# POWER.net
KiCad netlist of a schematic drawn in Altium Designer
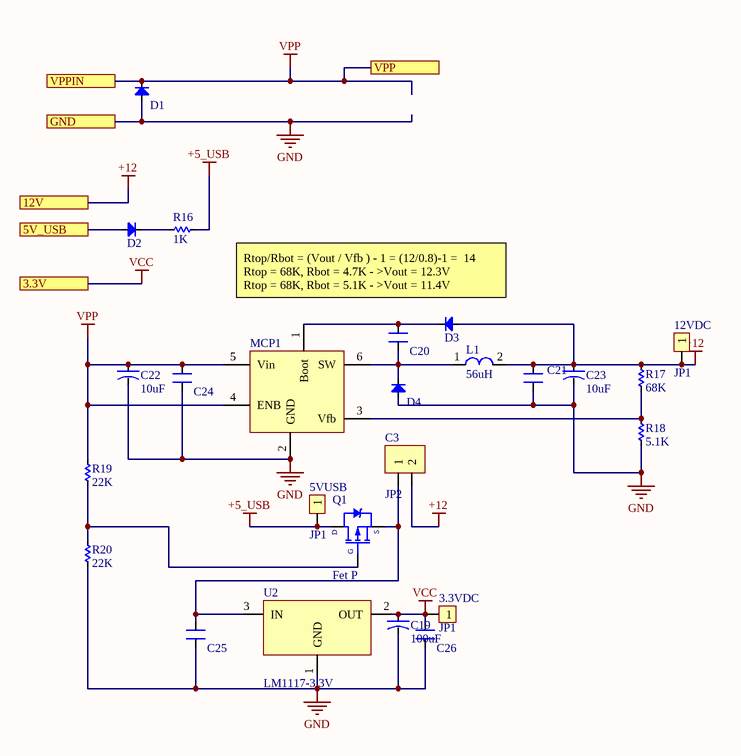
[diagram p0: POWER.SchDoc]

(export (version "E")
  (design (tool "Eeschema 10.0.6"))
  (components
    (comp (ref "3.3VDC")
      (value "JP1")
      (footprint "JP1-D1T")
      (description "WR-PHD 2.54 mm Angled Socket Header")
      (fields
        (field (name "MANUFACTURER") "Würth Elektronik eiSos GmbH")
        (field (name "PARTNO") "613002143121")
        (field (name "CREATED BY") "Karrer Zheng")
      )
      (libsource (lib "LIBRARY") (part "JP1"))
    )
    (comp (ref "5VUSB")
      (value "JP1")
      (footprint "JP1-D1T")
      (description "WR-PHD 2.54 mm Angled Socket Header")
      (fields
        (field (name "MANUFACTURER") "Würth Elektronik eiSos GmbH")
        (field (name "PARTNO") "613002143121")
        (field (name "CREATED BY") "Karrer Zheng")
      )
      (libsource (lib "") (part "JP1_1"))
    )
    (comp (ref "12VDC")
      (value "JP1")
      (footprint "JP1-D1T")
      (description "WR-PHD 2.54 mm Angled Socket Header")
      (fields
        (field (name "MANUFACTURER") "Würth Elektronik eiSos GmbH")
        (field (name "PARTNO") "613002143121")
        (field (name "CREATED BY") "Karrer Zheng")
      )
      (libsource (lib "") (part "JP1_1"))
    )
    (comp (ref "C3")
      (value "JP2")
      (footprint "JP2-CLOSED")
      (description "WR-PHD 2.54 mm Angled Socket Header")
      (fields
        (field (name "MANUFACTURER") "Würth Elektronik eiSos GmbH")
        (field (name "PARTNO") "613002143121")
        (field (name "CREATED BY") "Karrer Zheng")
      )
      (libsource (lib "LIBRARY") (part "JP2"))
    )
    (comp (ref "C19")
      (value "100uF")
      (footprint "CAP-ALU-SMD-D")
      (description "Polarized Capacitor (Axial)")
      (fields (field (name "PUBLISHER") "Altium Limited"))
      (libsource (lib "LIBRARY") (part "CN-ALU-SMD"))
    )
    (comp (ref "C20") (value "CN") (footprint "CN-SMD-0603_big") (libsource (lib "nhan") (part "CN")))
    (comp (ref "C21") (value "CN") (footprint "CN-SMD-0603_big") (libsource (lib "nhan") (part "CN")))
    (comp (ref "C22")
      (value "10uF")
      (footprint "CAP-ALU-SMD-6.3x7.7x2.2")
      (description "Polarized Capacitor (Axial)")
      (fields (field (name "PUBLISHER") "Altium Limited"))
      (libsource (lib "LIBRARY") (part "CN-ALU-SMD"))
    )
    (comp (ref "C23")
      (value "10uF")
      (footprint "CAP-ALU-SMD-6.3x7.7x2.2")
      (description "Polarized Capacitor (Axial)")
      (fields (field (name "PUBLISHER") "Altium Limited"))
      (libsource (lib "LIBRARY") (part "CN-ALU-SMD"))
    )
    (comp (ref "C24") (value "CN") (footprint "CN-SMD-0603_big") (libsource (lib "nhan") (part "CN")))
    (comp (ref "C25") (value "CN") (footprint "CN-SMD-0603_big") (libsource (lib "nhan") (part "CN")))
    (comp (ref "C26") (value "CN") (footprint "CN-SMD-0603_big") (libsource (lib "nhan") (part "CN")))
    (comp (ref "D1")
      (value "RB160M-60")
      (footprint "DIO-SMD-214AC")
      (description "Default Diode")
      (fields (field (name "PUBLISHER") "Altium Limited"))
      (libsource (lib "nhan") (part "Diode"))
    )
    (comp (ref "D2")
      (value "Diode")
      (footprint "DIO-SMD-123")
      (description "Default Diode")
      (fields (field (name "PUBLISHER") "Altium Limited"))
      (libsource (lib "nhan") (part "Diode"))
    )
    (comp (ref "D3")
      (value "Diode")
      (footprint "DIO-SMD-123")
      (description "Default Diode")
      (fields (field (name "PUBLISHER") "Altium Limited"))
      (libsource (lib "nhan") (part "Diode"))
    )
    (comp (ref "D4")
      (value "Diode")
      (footprint "DIO-SMD-123")
      (description "Default Diode")
      (fields (field (name "PUBLISHER") "Altium Limited"))
      (libsource (lib "nhan") (part "Diode"))
    )
    (comp (ref "L1")
      (value "56uH")
      (footprint "L_SMD")
      (description "https://www.thegioiic.com/products/cuon-cam-68uh-cd75-smd-7-8x7-5x5-0")
      (fields
        (field (name "PARTNO") "78477010")
        (field (name "MANUFACTURER") "Wurth Elektronik")
        (field (name "CREATED BY") "Baojun Chen")
      )
      (libsource (lib "nhan") (part "L-SMD-1"))
    )
    (comp (ref "MCP1") (value "MCP16331") (footprint "SOT23-6-") (libsource (lib "nhan") (part "MCP16331")))
    (comp (ref "Q1")
      (value "Fet P")
      (footprint "SOT23F")
      (description "HEXFET P-Channel Power MOSFET")
      (libsource (lib "nhan") (part "Fet P"))
    )
    (comp (ref "R16") (value "1K") (footprint "RES-SMD-0603_BIG") (libsource (lib "nhan") (part "R")))
    (comp (ref "R17") (value "68K") (footprint "RES-SMD-0603_BIG") (libsource (lib "nhan") (part "R")))
    (comp (ref "R18") (value "5.1K") (footprint "RES-SMD-0603_BIG") (libsource (lib "nhan") (part "R")))
    (comp (ref "R19") (value "22K") (footprint "RES-SMD-0603_BIG") (libsource (lib "nhan") (part "R")))
    (comp (ref "R20") (value "22K") (footprint "RES-SMD-0603_BIG") (libsource (lib "nhan") (part "R")))
    (comp (ref "U2")
      (value "LM1117-3.3V")
      (footprint "SOT223")
      (description "800mA Low-Dropout Linear Regulator")
      (fields (field (name "CREATOR") "Nguyen Ba Bien"))
      (libsource (lib "nhan") (part "LM1117"))
    )
  )
  (nets
    (net (code "1") (name "+5_USB") (class "Default")
      (node (ref "5VUSB") (pin "1") (pinfunction "1_1") (pintype "passive"))
      (node (ref "Q1") (pin "3") (pinfunction "D_3") (pintype "passive"))
      (node (ref "R16") (pin "2") (pinfunction "2_2") (pintype "passive"))
    )
    (net (code "2") (name "+12") (class "Default")
      (node (ref "12VDC") (pin "1") (pinfunction "1_1") (pintype "passive"))
      (node (ref "C21") (pin "2") (pinfunction "2_2") (pintype "passive"))
      (node (ref "C23") (pin "1") (pinfunction "1_1") (pintype "passive"))
      (node (ref "C3") (pin "2") (pinfunction "2_2") (pintype "passive"))
      (node (ref "D3") (pin "1") (pinfunction "A_1") (pintype "passive"))
      (node (ref "L1") (pin "2") (pinfunction "2_2") (pintype "passive"))
      (node (ref "R17") (pin "1") (pinfunction "1_1") (pintype "passive"))
    )
    (net (code "3") (name "/5V_USB") (class "Default")
      (node (ref "D2") (pin "1") (pinfunction "A_1") (pintype "passive"))
    )
    (net (code "4") (name "GND") (class "Default")
      (node (ref "C19") (pin "2") (pinfunction "2_2") (pintype "passive"))
      (node (ref "C21") (pin "1") (pinfunction "1_1") (pintype "passive"))
      (node (ref "C22") (pin "2") (pinfunction "2_2") (pintype "passive"))
      (node (ref "C23") (pin "2") (pinfunction "2_2") (pintype "passive"))
      (node (ref "C24") (pin "1") (pinfunction "1_1") (pintype "passive"))
      (node (ref "C25") (pin "1") (pinfunction "1_1") (pintype "passive"))
      (node (ref "C26") (pin "1") (pinfunction "1_1") (pintype "passive"))
      (node (ref "D1") (pin "1") (pinfunction "A_1") (pintype "passive"))
      (node (ref "D4") (pin "1") (pinfunction "A_1") (pintype "passive"))
      (node (ref "MCP1") (pin "2") (pinfunction "GND_2") (pintype "passive"))
      (node (ref "R18") (pin "2") (pinfunction "2_2") (pintype "passive"))
      (node (ref "R20") (pin "2") (pinfunction "2_2") (pintype "passive"))
      (node (ref "U2") (pin "1") (pinfunction "GND_1") (pintype "passive"))
    )
    (net (code "5") (name "Net-(D2-K)") (class "Default")
      (node (ref "D2") (pin "2") (pinfunction "K_2") (pintype "passive"))
      (node (ref "R16") (pin "1") (pinfunction "1_1") (pintype "passive"))
    )
    (net (code "6") (name "Net-(D3-K)") (class "Default")
      (node (ref "C20") (pin "2") (pinfunction "2_2") (pintype "passive"))
      (node (ref "D3") (pin "2") (pinfunction "K_2") (pintype "passive"))
      (node (ref "MCP1") (pin "1") (pinfunction "Boot_1") (pintype "passive"))
    )
    (net (code "7") (name "Net-(D4-K)") (class "Default")
      (node (ref "C20") (pin "1") (pinfunction "1_1") (pintype "passive"))
      (node (ref "D4") (pin "2") (pinfunction "K_2") (pintype "passive"))
      (node (ref "L1") (pin "1") (pinfunction "1_1") (pintype "passive"))
      (node (ref "MCP1") (pin "6") (pinfunction "SW_6") (pintype "passive"))
    )
    (net (code "8") (name "Net-(MCP1-Vfb)") (class "Default")
      (node (ref "MCP1") (pin "3") (pinfunction "Vfb_3") (pintype "passive"))
      (node (ref "R17") (pin "2") (pinfunction "2_2") (pintype "passive"))
      (node (ref "R18") (pin "1") (pinfunction "1_1") (pintype "passive"))
    )
    (net (code "9") (name "Net-(Q1-G)") (class "Default")
      (node (ref "Q1") (pin "1") (pinfunction "G_1") (pintype "passive"))
      (node (ref "R19") (pin "2") (pinfunction "2_2") (pintype "passive"))
      (node (ref "R20") (pin "1") (pinfunction "1_1") (pintype "passive"))
    )
    (net (code "10") (name "Net-(Q1-S)") (class "Default")
      (node (ref "C25") (pin "2") (pinfunction "2_2") (pintype "passive"))
      (node (ref "C3") (pin "1") (pinfunction "1_1") (pintype "passive"))
      (node (ref "Q1") (pin "2") (pinfunction "S_2") (pintype "passive"))
      (node (ref "U2") (pin "3") (pinfunction "IN_3") (pintype "passive"))
    )
    (net (code "11") (name "VCC") (class "Default")
      (node (ref "3.3VDC") (pin "1") (pinfunction "1_1") (pintype "passive"))
      (node (ref "C19") (pin "1") (pinfunction "1_1") (pintype "passive"))
      (node (ref "C26") (pin "2") (pinfunction "2_2") (pintype "passive"))
      (node (ref "U2") (pin "2") (pinfunction "OUT_2") (pintype "passive"))
    )
    (net (code "12") (name "VPP") (class "Default")
      (node (ref "C22") (pin "1") (pinfunction "1_1") (pintype "passive"))
      (node (ref "C24") (pin "2") (pinfunction "2_2") (pintype "passive"))
      (node (ref "D1") (pin "2") (pinfunction "K_2") (pintype "passive"))
      (node (ref "MCP1") (pin "4") (pinfunction "ENB_4") (pintype "passive"))
      (node (ref "MCP1") (pin "5") (pinfunction "Vin_5") (pintype "passive"))
      (node (ref "R19") (pin "1") (pinfunction "1_1") (pintype "passive"))
    )
  )
)
